# autonomous_vehicle_controller.net
KiCad netlist of a schematic drawn in EAGLE
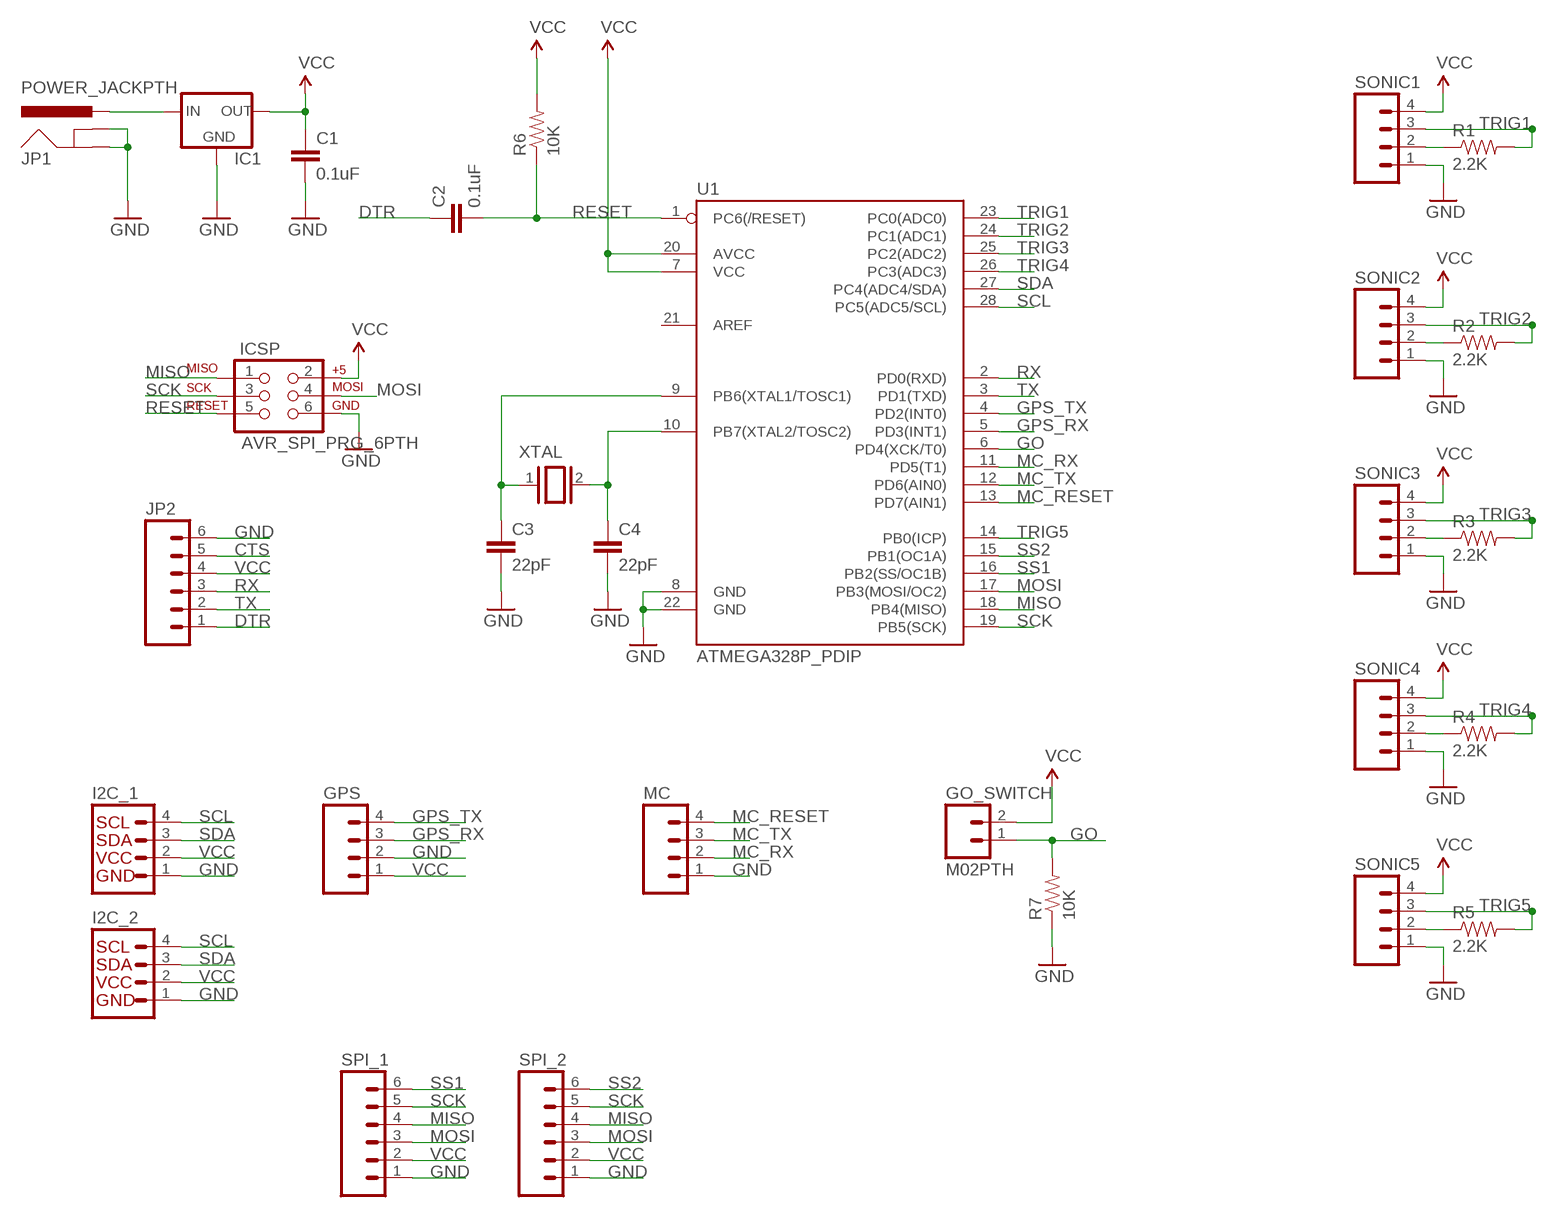
[diagram p0: schematic, sheet 1]

(export (version "E")
  (design (tool "Eeschema 10.0.6"))
  (components
    (comp (ref "C1")
      (value "0.1uF")
      (footprint "eagle-import:CAP-PTH-SMALL")
      (libsource (lib "eagle-import") (part "CAPPTH"))
    )
    (comp (ref "C2")
      (value "0.1uF")
      (footprint "eagle-import:CAP-PTH-SMALL")
      (libsource (lib "eagle-import") (part "CAPPTH"))
    )
    (comp (ref "C3")
      (value "22pF")
      (footprint "eagle-import:CAP-PTH-SMALL")
      (libsource (lib "eagle-import") (part "SparkFun-Passives_CAPPTH"))
    )
    (comp (ref "C4")
      (value "22pF")
      (footprint "eagle-import:CAP-PTH-SMALL")
      (libsource (lib "eagle-import") (part "SparkFun-Passives_CAPPTH"))
    )
    (comp (ref "GO_SWITCH")
      (value "M02PTH")
      (footprint "eagle-import:1X02")
      (libsource (lib "eagle-import") (part "M02PTH"))
    )
    (comp (ref "GPS")
      (value "M04PTH")
      (footprint "eagle-import:1X04")
      (libsource (lib "eagle-import") (part "M04PTH"))
    )
    (comp (ref "I2C_1")
      (value "I2C_STANDARD")
      (footprint "eagle-import:1X04")
      (libsource (lib "eagle-import") (part "I2C_STANDARD"))
    )
    (comp (ref "I2C_2")
      (value "I2C_STANDARD")
      (footprint "eagle-import:1X04")
      (libsource (lib "eagle-import") (part "I2C_STANDARD"))
    )
    (comp (ref "IC1")
      (value "V_REG_78XXSIDE")
      (footprint "eagle-import:78XXL")
      (libsource (lib "eagle-import") (part "V_REG_78XXSIDE"))
    )
    (comp (ref "ICSP")
      (value "AVR_SPI_PRG_6PTH")
      (footprint "eagle-import:2X3")
      (libsource (lib "eagle-import") (part "AVR_SPI_PRG_6PTH"))
    )
    (comp (ref "JP1")
      (value "POWER_JACKPTH")
      (footprint "eagle-import:POWER_JACK_PTH")
      (libsource (lib "eagle-import") (part "POWER_JACKPTH"))
    )
    (comp (ref "JP2")
      (value "M06SILK_FEMALE_PTH")
      (footprint "eagle-import:1X06")
      (libsource (lib "eagle-import") (part "M06SILK_FEMALE_PTH"))
    )
    (comp (ref "MC")
      (value "M04PTH")
      (footprint "eagle-import:1X04")
      (libsource (lib "eagle-import") (part "M04PTH"))
    )
    (comp (ref "R1")
      (value "2.2K")
      (footprint "eagle-import:AXIAL-0.4")
      (libsource (lib "eagle-import") (part "RESISTORPTH-1/4W"))
    )
    (comp (ref "R2")
      (value "2.2K")
      (footprint "eagle-import:AXIAL-0.4")
      (libsource (lib "eagle-import") (part "RESISTORPTH-1/4W"))
    )
    (comp (ref "R3")
      (value "2.2K")
      (footprint "eagle-import:AXIAL-0.4")
      (libsource (lib "eagle-import") (part "RESISTORPTH-1/4W"))
    )
    (comp (ref "R4")
      (value "2.2K")
      (footprint "eagle-import:AXIAL-0.4")
      (libsource (lib "eagle-import") (part "RESISTORPTH-1/4W"))
    )
    (comp (ref "R5")
      (value "2.2K")
      (footprint "eagle-import:AXIAL-0.4")
      (libsource (lib "eagle-import") (part "RESISTORPTH-1/4W"))
    )
    (comp (ref "R6")
      (value "10K")
      (footprint "eagle-import:AXIAL-0.4")
      (libsource (lib "eagle-import") (part "RESISTORPTH-1/4W"))
    )
    (comp (ref "R7")
      (value "10K")
      (footprint "eagle-import:AXIAL-0.4")
      (libsource (lib "eagle-import") (part "RESISTORPTH-1/4W"))
    )
    (comp (ref "SONIC1")
      (value "M04PTH")
      (footprint "eagle-import:1X04")
      (libsource (lib "eagle-import") (part "M04PTH"))
    )
    (comp (ref "SONIC2")
      (value "M04PTH")
      (footprint "eagle-import:1X04")
      (libsource (lib "eagle-import") (part "M04PTH"))
    )
    (comp (ref "SONIC3")
      (value "M04PTH")
      (footprint "eagle-import:1X04")
      (libsource (lib "eagle-import") (part "M04PTH"))
    )
    (comp (ref "SONIC4")
      (value "M04PTH")
      (footprint "eagle-import:1X04")
      (libsource (lib "eagle-import") (part "M04PTH"))
    )
    (comp (ref "SONIC5")
      (value "M04PTH")
      (footprint "eagle-import:1X04")
      (libsource (lib "eagle-import") (part "M04PTH"))
    )
    (comp (ref "SPI_1")
      (value "M06SILK_FEMALE_PTH")
      (footprint "eagle-import:1X06")
      (libsource (lib "eagle-import") (part "M06SILK_FEMALE_PTH"))
    )
    (comp (ref "SPI_2")
      (value "M06SILK_FEMALE_PTH")
      (footprint "eagle-import:1X06")
      (libsource (lib "eagle-import") (part "M06SILK_FEMALE_PTH"))
    )
    (comp (ref "U1")
      (value "ATMEGA328P_PDIP")
      (footprint "eagle-import:DIL28-3")
      (libsource (lib "eagle-import") (part "ATMEGA328P_PDIP"))
    )
    (comp (ref "XTAL")
      (value "XTAL/S")
      (footprint "eagle-import:QS")
      (libsource (lib "eagle-import") (part "XTAL/S"))
    )
  )
  (nets
    (net (code "1") (name "/CTS") (class "Default")
      (node (ref "JP2") (pin "5") (pinfunction "5_5") (pintype "passive"))
    )
    (net (code "2") (name "/DTR") (class "Default")
      (node (ref "C2") (pin "1") (pinfunction "1_1") (pintype "passive"))
      (node (ref "JP2") (pin "1") (pinfunction "1_1") (pintype "passive"))
    )
    (net (code "3") (name "/GO") (class "Default")
      (node (ref "GO_SWITCH") (pin "1") (pinfunction "1_1") (pintype "passive"))
      (node (ref "R7") (pin "P$2") (pinfunction "2_P$2") (pintype "passive"))
      (node (ref "U1") (pin "6") (pinfunction "PD4(XCK/T0)_6") (pintype "bidirectional"))
    )
    (net (code "4") (name "/GPS_RX") (class "Default")
      (node (ref "GPS") (pin "3") (pinfunction "3_3") (pintype "passive"))
      (node (ref "U1") (pin "5") (pinfunction "PD3(INT1)_5") (pintype "bidirectional"))
    )
    (net (code "5") (name "/GPS_TX") (class "Default")
      (node (ref "GPS") (pin "4") (pinfunction "4_4") (pintype "passive"))
      (node (ref "U1") (pin "4") (pinfunction "PD2(INT0)_4") (pintype "bidirectional"))
    )
    (net (code "6") (name "/MC_RESET") (class "Default")
      (node (ref "MC") (pin "4") (pinfunction "4_4") (pintype "passive"))
      (node (ref "U1") (pin "13") (pinfunction "PD7(AIN1)_13") (pintype "bidirectional"))
    )
    (net (code "7") (name "/MC_RX") (class "Default")
      (node (ref "MC") (pin "2") (pinfunction "2_2") (pintype "passive"))
      (node (ref "U1") (pin "11") (pinfunction "PD5(T1)_11") (pintype "bidirectional"))
    )
    (net (code "8") (name "/MC_TX") (class "Default")
      (node (ref "MC") (pin "3") (pinfunction "3_3") (pintype "passive"))
      (node (ref "U1") (pin "12") (pinfunction "PD6(AIN0)_12") (pintype "bidirectional"))
    )
    (net (code "9") (name "/MISO") (class "Default")
      (node (ref "ICSP") (pin "1") (pinfunction "1_1") (pintype "passive"))
      (node (ref "SPI_1") (pin "4") (pinfunction "4_4") (pintype "passive"))
      (node (ref "SPI_2") (pin "4") (pinfunction "4_4") (pintype "passive"))
      (node (ref "U1") (pin "18") (pinfunction "PB4(MISO)_18") (pintype "bidirectional"))
    )
    (net (code "10") (name "/MOSI") (class "Default")
      (node (ref "ICSP") (pin "4") (pinfunction "4_4") (pintype "passive"))
      (node (ref "SPI_1") (pin "3") (pinfunction "3_3") (pintype "passive"))
      (node (ref "SPI_2") (pin "3") (pinfunction "3_3") (pintype "passive"))
      (node (ref "U1") (pin "17") (pinfunction "PB3(MOSI/OC2)_17") (pintype "bidirectional"))
    )
    (net (code "11") (name "/RESET") (class "Default")
      (node (ref "C2") (pin "2") (pinfunction "2_2") (pintype "passive"))
      (node (ref "ICSP") (pin "5") (pinfunction "5_5") (pintype "passive"))
      (node (ref "R6") (pin "P$1") (pinfunction "1_P$1") (pintype "passive"))
      (node (ref "U1") (pin "1") (pinfunction "PC6(/RESET)_1") (pintype "bidirectional"))
    )
    (net (code "12") (name "/RX") (class "Default")
      (node (ref "JP2") (pin "3") (pinfunction "3_3") (pintype "passive"))
      (node (ref "U1") (pin "2") (pinfunction "PD0(RXD)_2") (pintype "bidirectional"))
    )
    (net (code "13") (name "/SCK") (class "Default")
      (node (ref "ICSP") (pin "3") (pinfunction "3_3") (pintype "passive"))
      (node (ref "SPI_1") (pin "5") (pinfunction "5_5") (pintype "passive"))
      (node (ref "SPI_2") (pin "5") (pinfunction "5_5") (pintype "passive"))
      (node (ref "U1") (pin "19") (pinfunction "PB5(SCK)_19") (pintype "bidirectional"))
    )
    (net (code "14") (name "/SCL") (class "Default")
      (node (ref "I2C_1") (pin "4") (pinfunction "4_4") (pintype "passive"))
      (node (ref "I2C_2") (pin "4") (pinfunction "4_4") (pintype "passive"))
      (node (ref "U1") (pin "28") (pinfunction "PC5(ADC5/SCL)_28") (pintype "bidirectional"))
    )
    (net (code "15") (name "/SDA") (class "Default")
      (node (ref "I2C_1") (pin "3") (pinfunction "3_3") (pintype "passive"))
      (node (ref "I2C_2") (pin "3") (pinfunction "3_3") (pintype "passive"))
      (node (ref "U1") (pin "27") (pinfunction "PC4(ADC4/SDA)_27") (pintype "bidirectional"))
    )
    (net (code "16") (name "/SS1") (class "Default")
      (node (ref "SPI_1") (pin "6") (pinfunction "6_6") (pintype "passive"))
      (node (ref "U1") (pin "16") (pinfunction "PB2(SS/OC1B)_16") (pintype "bidirectional"))
    )
    (net (code "17") (name "/SS2") (class "Default")
      (node (ref "SPI_2") (pin "6") (pinfunction "6_6") (pintype "passive"))
      (node (ref "U1") (pin "15") (pinfunction "PB1(OC1A)_15") (pintype "bidirectional"))
    )
    (net (code "18") (name "/TRIG1") (class "Default")
      (node (ref "R1") (pin "P$2") (pinfunction "2_P$2") (pintype "passive"))
      (node (ref "SONIC1") (pin "3") (pinfunction "3_3") (pintype "passive"))
      (node (ref "U1") (pin "23") (pinfunction "PC0(ADC0)_23") (pintype "bidirectional"))
    )
    (net (code "19") (name "/TRIG2") (class "Default")
      (node (ref "R2") (pin "P$2") (pinfunction "2_P$2") (pintype "passive"))
      (node (ref "SONIC2") (pin "3") (pinfunction "3_3") (pintype "passive"))
      (node (ref "U1") (pin "24") (pinfunction "PC1(ADC1)_24") (pintype "bidirectional"))
    )
    (net (code "20") (name "/TRIG3") (class "Default")
      (node (ref "R3") (pin "P$2") (pinfunction "2_P$2") (pintype "passive"))
      (node (ref "SONIC3") (pin "3") (pinfunction "3_3") (pintype "passive"))
      (node (ref "U1") (pin "25") (pinfunction "PC2(ADC2)_25") (pintype "bidirectional"))
    )
    (net (code "21") (name "/TRIG4") (class "Default")
      (node (ref "R4") (pin "P$2") (pinfunction "2_P$2") (pintype "passive"))
      (node (ref "SONIC4") (pin "3") (pinfunction "3_3") (pintype "passive"))
      (node (ref "U1") (pin "26") (pinfunction "PC3(ADC3)_26") (pintype "bidirectional"))
    )
    (net (code "22") (name "/TRIG5") (class "Default")
      (node (ref "R5") (pin "P$2") (pinfunction "2_P$2") (pintype "passive"))
      (node (ref "SONIC5") (pin "3") (pinfunction "3_3") (pintype "passive"))
      (node (ref "U1") (pin "14") (pinfunction "PB0(ICP)_14") (pintype "bidirectional"))
    )
    (net (code "23") (name "/TX") (class "Default")
      (node (ref "JP2") (pin "2") (pinfunction "2_2") (pintype "passive"))
      (node (ref "U1") (pin "3") (pinfunction "PD1(TXD)_3") (pintype "bidirectional"))
    )
    (net (code "24") (name "GND") (class "Default")
      (node (ref "C1") (pin "2") (pinfunction "2_2") (pintype "passive"))
      (node (ref "C3") (pin "2") (pinfunction "2_2") (pintype "passive"))
      (node (ref "C4") (pin "2") (pinfunction "2_2") (pintype "passive"))
      (node (ref "GPS") (pin "2") (pinfunction "2_2") (pintype "passive"))
      (node (ref "I2C_1") (pin "1") (pinfunction "1_1") (pintype "passive"))
      (node (ref "I2C_2") (pin "1") (pinfunction "1_1") (pintype "passive"))
      (node (ref "IC1") (pin "GND") (pinfunction "GND_GND") (pintype "input"))
      (node (ref "ICSP") (pin "6") (pinfunction "6_6") (pintype "passive"))
      (node (ref "JP1") (pin "GND") (pinfunction "GND_GND") (pintype "bidirectional"))
      (node (ref "JP1") (pin "GNDBREAK") (pinfunction "GNDBREAK_GNDBREAK") (pintype "bidirectional"))
      (node (ref "JP2") (pin "6") (pinfunction "6_6") (pintype "passive"))
      (node (ref "MC") (pin "1") (pinfunction "1_1") (pintype "passive"))
      (node (ref "R7") (pin "P$1") (pinfunction "1_P$1") (pintype "passive"))
      (node (ref "SONIC1") (pin "1") (pinfunction "1_1") (pintype "passive"))
      (node (ref "SONIC2") (pin "1") (pinfunction "1_1") (pintype "passive"))
      (node (ref "SONIC3") (pin "1") (pinfunction "1_1") (pintype "passive"))
      (node (ref "SONIC4") (pin "1") (pinfunction "1_1") (pintype "passive"))
      (node (ref "SONIC5") (pin "1") (pinfunction "1_1") (pintype "passive"))
      (node (ref "SPI_1") (pin "1") (pinfunction "1_1") (pintype "passive"))
      (node (ref "SPI_2") (pin "1") (pinfunction "1_1") (pintype "passive"))
      (node (ref "U1") (pin "22") (pinfunction "GND_22") (pintype "bidirectional"))
      (node (ref "U1") (pin "8") (pinfunction "GND_8") (pintype "bidirectional"))
    )
    (net (code "25") (name "Net-(IC1-PadIN)") (class "Default")
      (node (ref "IC1") (pin "IN") (pinfunction "IN_IN") (pintype "input"))
      (node (ref "JP1") (pin "PWR") (pinfunction "PWR_PWR") (pintype "bidirectional"))
    )
    (net (code "26") (name "Net-(R1-1)") (class "Default")
      (node (ref "R1") (pin "P$1") (pinfunction "1_P$1") (pintype "passive"))
      (node (ref "SONIC1") (pin "2") (pinfunction "2_2") (pintype "passive"))
    )
    (net (code "27") (name "Net-(R2-1)") (class "Default")
      (node (ref "R2") (pin "P$1") (pinfunction "1_P$1") (pintype "passive"))
      (node (ref "SONIC2") (pin "2") (pinfunction "2_2") (pintype "passive"))
    )
    (net (code "28") (name "Net-(R3-1)") (class "Default")
      (node (ref "R3") (pin "P$1") (pinfunction "1_P$1") (pintype "passive"))
      (node (ref "SONIC3") (pin "2") (pinfunction "2_2") (pintype "passive"))
    )
    (net (code "29") (name "Net-(R4-1)") (class "Default")
      (node (ref "R4") (pin "P$1") (pinfunction "1_P$1") (pintype "passive"))
      (node (ref "SONIC4") (pin "2") (pinfunction "2_2") (pintype "passive"))
    )
    (net (code "30") (name "Net-(R5-1)") (class "Default")
      (node (ref "R5") (pin "P$1") (pinfunction "1_P$1") (pintype "passive"))
      (node (ref "SONIC5") (pin "2") (pinfunction "2_2") (pintype "passive"))
    )
    (net (code "31") (name "Net-(U1-PB6(XTAL1{slash}TOSC1))") (class "Default")
      (node (ref "C3") (pin "1") (pinfunction "1_1") (pintype "passive"))
      (node (ref "U1") (pin "9") (pinfunction "PB6(XTAL1/TOSC1)_9") (pintype "bidirectional"))
      (node (ref "XTAL") (pin "1") (pinfunction "1_1") (pintype "passive"))
    )
    (net (code "32") (name "Net-(U1-PB7(XTAL2{slash}TOSC2))") (class "Default")
      (node (ref "C4") (pin "1") (pinfunction "1_1") (pintype "passive"))
      (node (ref "U1") (pin "10") (pinfunction "PB7(XTAL2/TOSC2)_10") (pintype "bidirectional"))
      (node (ref "XTAL") (pin "2") (pinfunction "2_2") (pintype "passive"))
    )
    (net (code "33") (name "VCC") (class "Default")
      (node (ref "C1") (pin "1") (pinfunction "1_1") (pintype "passive"))
      (node (ref "GO_SWITCH") (pin "2") (pinfunction "2_2") (pintype "passive"))
      (node (ref "GPS") (pin "1") (pinfunction "1_1") (pintype "passive"))
      (node (ref "I2C_1") (pin "2") (pinfunction "2_2") (pintype "passive"))
      (node (ref "I2C_2") (pin "2") (pinfunction "2_2") (pintype "passive"))
      (node (ref "IC1") (pin "OUT") (pinfunction "OUT_OUT") (pintype "output"))
      (node (ref "ICSP") (pin "2") (pinfunction "2_2") (pintype "passive"))
      (node (ref "JP2") (pin "4") (pinfunction "4_4") (pintype "passive"))
      (node (ref "R6") (pin "P$2") (pinfunction "2_P$2") (pintype "passive"))
      (node (ref "SONIC1") (pin "4") (pinfunction "4_4") (pintype "passive"))
      (node (ref "SONIC2") (pin "4") (pinfunction "4_4") (pintype "passive"))
      (node (ref "SONIC3") (pin "4") (pinfunction "4_4") (pintype "passive"))
      (node (ref "SONIC4") (pin "4") (pinfunction "4_4") (pintype "passive"))
      (node (ref "SONIC5") (pin "4") (pinfunction "4_4") (pintype "passive"))
      (node (ref "SPI_1") (pin "2") (pinfunction "2_2") (pintype "passive"))
      (node (ref "SPI_2") (pin "2") (pinfunction "2_2") (pintype "passive"))
      (node (ref "U1") (pin "20") (pinfunction "AVCC_20") (pintype "bidirectional"))
      (node (ref "U1") (pin "7") (pinfunction "VCC_7") (pintype "bidirectional"))
    )
    (net (code "34") (name "unconnected-(U1-AREF-Pad21)") (class "Default")
      (node (ref "U1") (pin "21") (pinfunction "AREF_21") (pintype "bidirectional"))
    )
  )
)
